# brainslug_v2.net
KiCad netlist of a schematic drawn in EAGLE
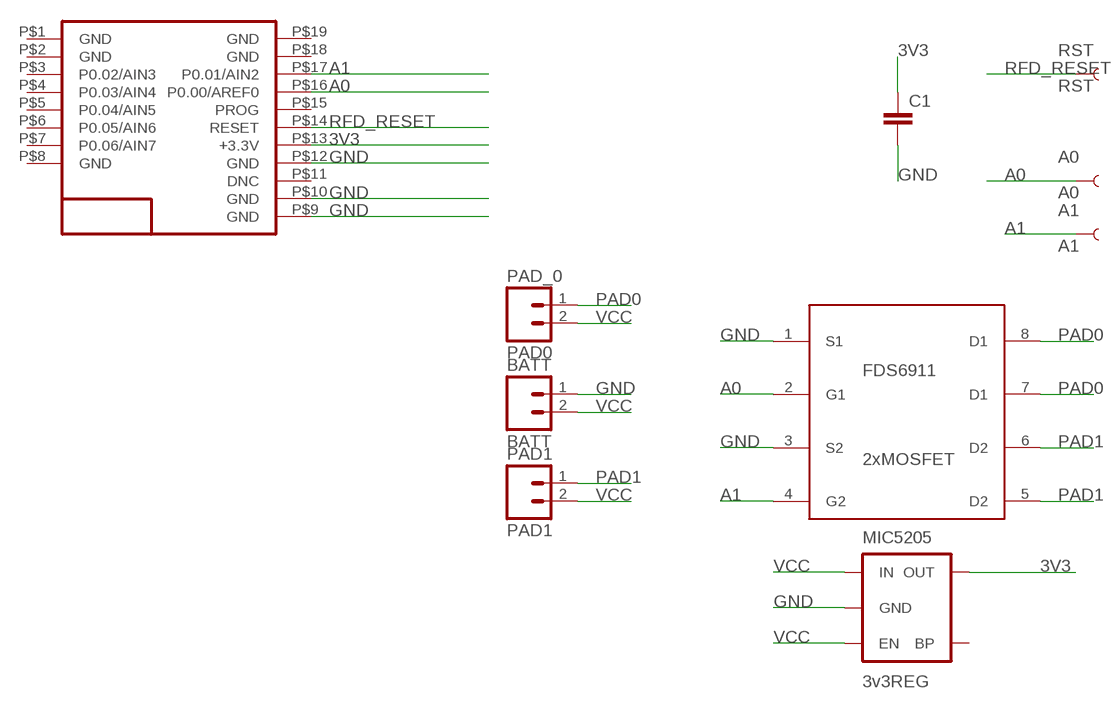
[diagram p0: schematic, sheet 1]

(export (version "E")
  (design (tool "Eeschema 10.0.6"))
  (components
    (comp (ref "A0")
      (value "A0")
      (footprint "eagle-import:PAD.03X.03")
      (libsource (lib "eagle-import") (part "TEST-POINT3"))
    )
    (comp (ref "A1")
      (value "A1")
      (footprint "eagle-import:PAD.03X.03")
      (libsource (lib "eagle-import") (part "TEST-POINT3"))
    )
    (comp (ref "BATT")
      (value "BATT")
      (footprint "eagle-import:JST-2-SMD")
      (libsource (lib "eagle-import") (part "M02-JST-2MM-SMT"))
    )
    (comp (ref "C1")
      (value "CAP")
      (footprint "eagle-import:C3216")
      (libsource (lib "eagle-import") (part "CAP"))
    )
    (comp (ref "FDS6911")
      (value "2xMOSFET")
      (footprint "eagle-import:SO8")
      (libsource (lib "eagle-import") (part "FDS6911"))
    )
    (comp (ref "MIC5205")
      (value "3v3REG")
      (footprint "eagle-import:SOT23-5")
      (libsource (lib "eagle-import") (part "MIC52053.3V"))
    )
    (comp (ref "PAD1")
      (value "PAD1")
      (footprint "eagle-import:JST-2-SMD")
      (libsource (lib "eagle-import") (part "M02-JST-2MM-SMT"))
    )
    (comp (ref "PAD_0")
      (value "PAD0")
      (footprint "eagle-import:JST-2-SMD")
      (libsource (lib "eagle-import") (part "M02-JST-2MM-SMT"))
    )
    (comp (ref "RST")
      (value "RST")
      (footprint "eagle-import:PAD.03X.03")
      (libsource (lib "eagle-import") (part "TEST-POINT3"))
    )
    (comp (ref "U$1")
      (value "RFD22301")
      (footprint "eagle-import:RFD21733")
      (libsource (lib "eagle-import") (part "RFD22301"))
    )
  )
  (nets
    (net (code "1") (name "/3V3") (class "Default")
      (node (ref "C1") (pin "1") (pinfunction "1_1") (pintype "passive"))
      (node (ref "MIC5205") (pin "5") (pinfunction "OUT_5") (pintype "passive"))
      (node (ref "U$1") (pin "P$13") (pinfunction "+3.3V_P$13") (pintype "bidirectional"))
    )
    (net (code "2") (name "/A0") (class "Default")
      (node (ref "A0") (pin "P$1") (pinfunction "1_P$1") (pintype "bidirectional"))
      (node (ref "FDS6911") (pin "2") (pinfunction "G1_2") (pintype "bidirectional"))
      (node (ref "U$1") (pin "P$16") (pinfunction "P0.00/AREF0_P$16") (pintype "bidirectional"))
    )
    (net (code "3") (name "/A1") (class "Default")
      (node (ref "A1") (pin "P$1") (pinfunction "1_P$1") (pintype "bidirectional"))
      (node (ref "FDS6911") (pin "4") (pinfunction "G2_4") (pintype "bidirectional"))
      (node (ref "U$1") (pin "P$17") (pinfunction "P0.01/AIN2_P$17") (pintype "bidirectional"))
    )
    (net (code "4") (name "/GND") (class "Default")
      (node (ref "BATT") (pin "1") (pinfunction "2_1") (pintype "passive"))
      (node (ref "C1") (pin "2") (pinfunction "2_2") (pintype "passive"))
      (node (ref "FDS6911") (pin "1") (pinfunction "S1_1") (pintype "bidirectional"))
      (node (ref "FDS6911") (pin "3") (pinfunction "S2_3") (pintype "bidirectional"))
      (node (ref "MIC5205") (pin "2") (pinfunction "GND_2") (pintype "input"))
      (node (ref "U$1") (pin "P$10") (pinfunction "GND_P$10") (pintype "bidirectional"))
      (node (ref "U$1") (pin "P$12") (pinfunction "GND_P$12") (pintype "bidirectional"))
      (node (ref "U$1") (pin "P$9") (pinfunction "GND_P$9") (pintype "bidirectional"))
    )
    (net (code "5") (name "/PAD0") (class "Default")
      (node (ref "FDS6911") (pin "7") (pinfunction "D1_7") (pintype "bidirectional"))
      (node (ref "FDS6911") (pin "8") (pinfunction "D1_8") (pintype "bidirectional"))
      (node (ref "PAD_0") (pin "1") (pinfunction "2_1") (pintype "passive"))
    )
    (net (code "6") (name "/PAD1") (class "Default")
      (node (ref "FDS6911") (pin "5") (pinfunction "D2_5") (pintype "bidirectional"))
      (node (ref "FDS6911") (pin "6") (pinfunction "D2_6") (pintype "bidirectional"))
      (node (ref "PAD1") (pin "1") (pinfunction "2_1") (pintype "passive"))
    )
    (net (code "7") (name "/RFD_RESET") (class "Default")
      (node (ref "RST") (pin "P$1") (pinfunction "1_P$1") (pintype "bidirectional"))
      (node (ref "U$1") (pin "P$14") (pinfunction "RESET_P$14") (pintype "bidirectional"))
    )
    (net (code "8") (name "/VCC") (class "Default")
      (node (ref "BATT") (pin "2") (pinfunction "1_2") (pintype "passive"))
      (node (ref "MIC5205") (pin "1") (pinfunction "IN_1") (pintype "input"))
      (node (ref "MIC5205") (pin "3") (pinfunction "EN_3") (pintype "input"))
      (node (ref "PAD1") (pin "2") (pinfunction "1_2") (pintype "passive"))
      (node (ref "PAD_0") (pin "2") (pinfunction "1_2") (pintype "passive"))
    )
    (net (code "9") (name "unconnected-(MIC5205-BP-Pad4)") (class "Default")
      (node (ref "MIC5205") (pin "4") (pinfunction "BP_4") (pintype "input"))
    )
    (net (code "10") (name "unconnected-(U$1-DNC-PadP$11)") (class "Default")
      (node (ref "U$1") (pin "P$11") (pinfunction "DNC_P$11") (pintype "bidirectional"))
    )
    (net (code "11") (name "unconnected-(U$1-GND-PadP$1)") (class "Default")
      (node (ref "U$1") (pin "P$1") (pinfunction "GND_P$1") (pintype "bidirectional"))
    )
    (net (code "12") (name "unconnected-(U$1-GND-PadP$2)") (class "Default")
      (node (ref "U$1") (pin "P$2") (pinfunction "GND_P$2") (pintype "bidirectional"))
    )
    (net (code "13") (name "unconnected-(U$1-GND-PadP$8)") (class "Default")
      (node (ref "U$1") (pin "P$8") (pinfunction "GND_P$8") (pintype "bidirectional"))
    )
    (net (code "14") (name "unconnected-(U$1-GND-PadP$18)") (class "Default")
      (node (ref "U$1") (pin "P$18") (pinfunction "GND_P$18") (pintype "bidirectional"))
    )
    (net (code "15") (name "unconnected-(U$1-GND-PadP$19)") (class "Default")
      (node (ref "U$1") (pin "P$19") (pinfunction "GND_P$19") (pintype "bidirectional"))
    )
    (net (code "16") (name "unconnected-(U$1-P0.02{slash}AIN3-PadP$3)") (class "Default")
      (node (ref "U$1") (pin "P$3") (pinfunction "P0.02/AIN3_P$3") (pintype "bidirectional"))
    )
    (net (code "17") (name "unconnected-(U$1-P0.03{slash}AIN4-PadP$4)") (class "Default")
      (node (ref "U$1") (pin "P$4") (pinfunction "P0.03/AIN4_P$4") (pintype "bidirectional"))
    )
    (net (code "18") (name "unconnected-(U$1-P0.04{slash}AIN5-PadP$5)") (class "Default")
      (node (ref "U$1") (pin "P$5") (pinfunction "P0.04/AIN5_P$5") (pintype "bidirectional"))
    )
    (net (code "19") (name "unconnected-(U$1-P0.05{slash}AIN6-PadP$6)") (class "Default")
      (node (ref "U$1") (pin "P$6") (pinfunction "P0.05/AIN6_P$6") (pintype "bidirectional"))
    )
    (net (code "20") (name "unconnected-(U$1-P0.06{slash}AIN7-PadP$7)") (class "Default")
      (node (ref "U$1") (pin "P$7") (pinfunction "P0.06/AIN7_P$7") (pintype "bidirectional"))
    )
    (net (code "21") (name "unconnected-(U$1-PROG-PadP$15)") (class "Default")
      (node (ref "U$1") (pin "P$15") (pinfunction "PROG_P$15") (pintype "bidirectional"))
    )
  )
)
